# ME433_chip_board.net
KiCad netlist of a schematic drawn in EAGLE
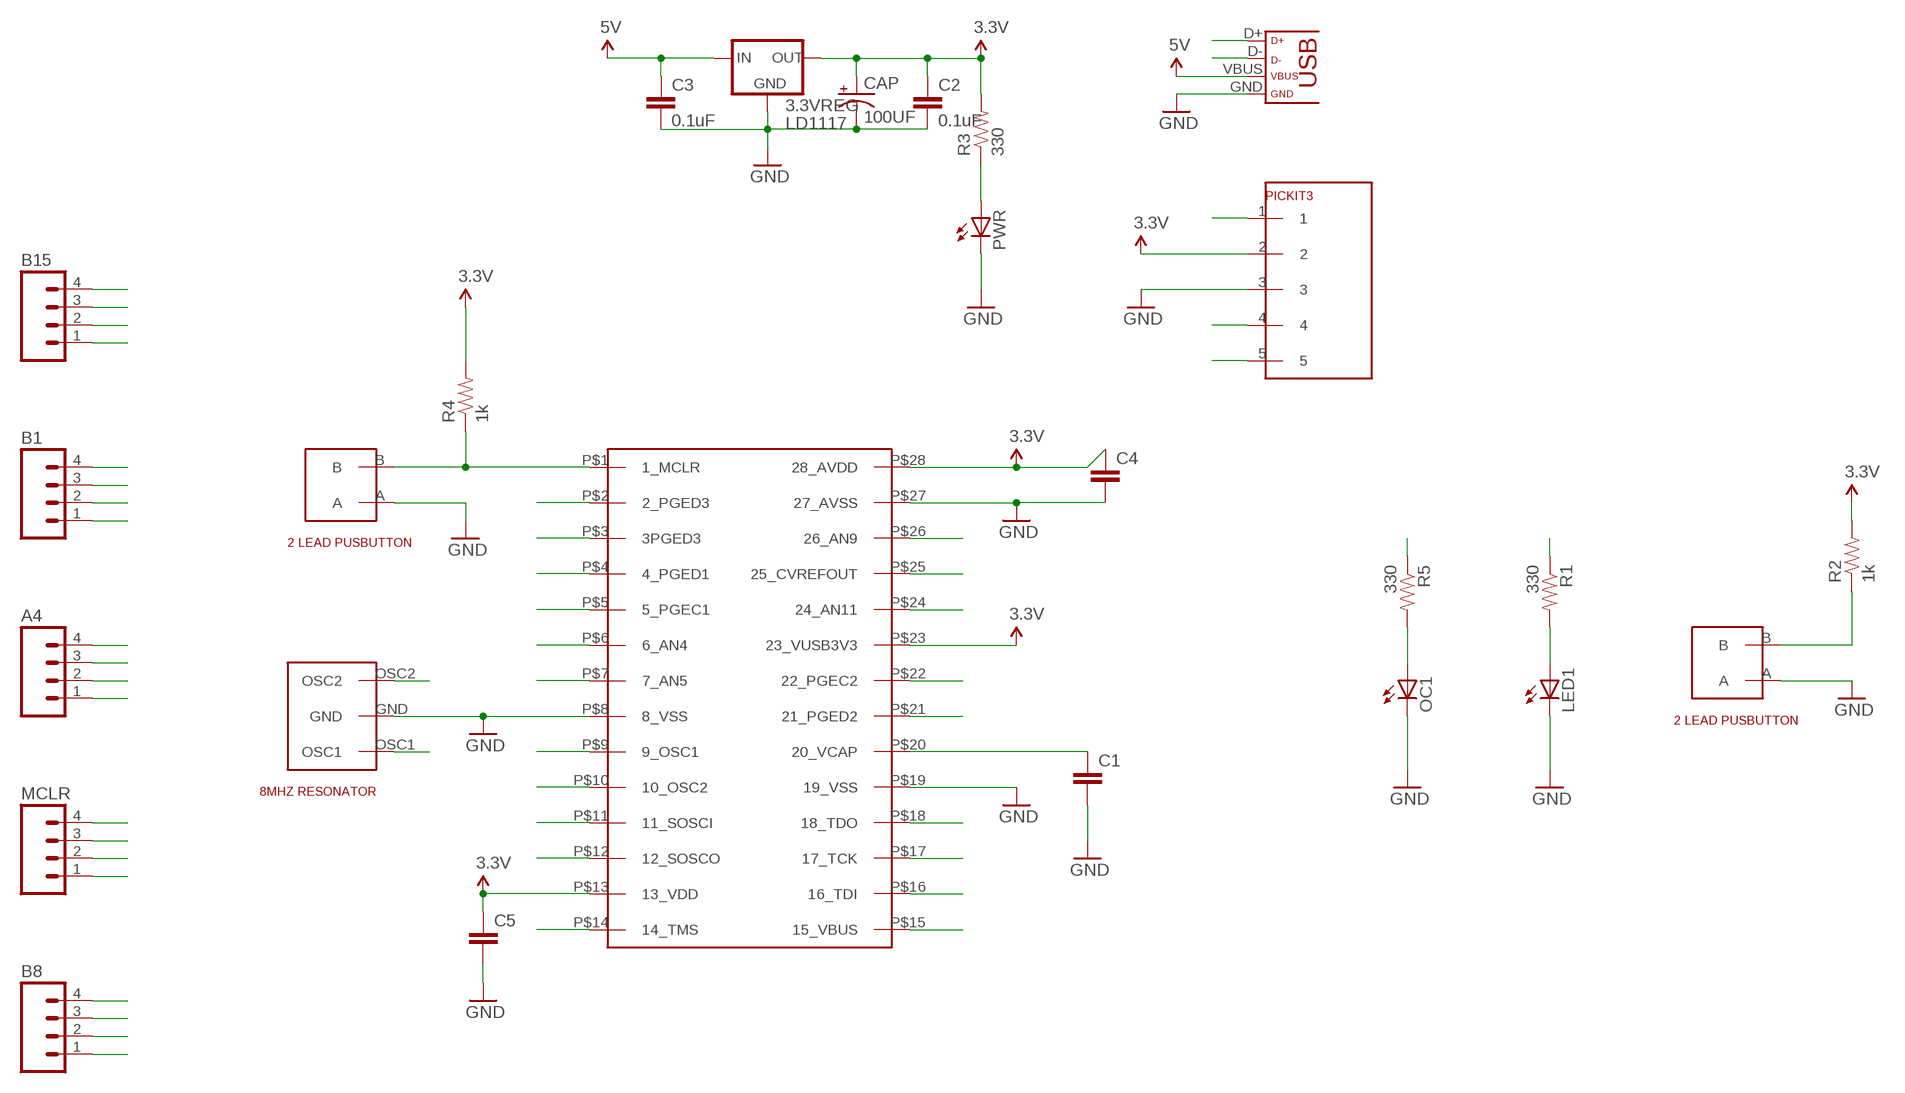
[diagram p0: schematic, sheet 1]

(export (version "E")
  (design (tool "Eeschema 10.0.6"))
  (components
    (comp (ref "3.3VREG")
      (value "LD1117")
      (footprint "eagle-import:TO220")
      (libsource (lib "eagle-import") (part "LD1117"))
    )
    (comp (ref "A4")
      (value "M04PTH")
      (footprint "eagle-import:1X04")
      (libsource (lib "eagle-import") (part "M04PTH"))
    )
    (comp (ref "B1")
      (value "M04PTH")
      (footprint "eagle-import:1X04")
      (libsource (lib "eagle-import") (part "M04PTH"))
    )
    (comp (ref "B8")
      (value "M04PTH")
      (footprint "eagle-import:1X04")
      (libsource (lib "eagle-import") (part "M04PTH"))
    )
    (comp (ref "B15")
      (value "M04PTH")
      (footprint "eagle-import:1X04")
      (libsource (lib "eagle-import") (part "M04PTH"))
    )
    (comp (ref "C1")
      (value "CAP0603-CAP")
      (footprint "eagle-import:0603-CAP")
      (libsource (lib "eagle-import") (part "CAP0603-CAP"))
    )
    (comp (ref "C2")
      (value "0.1uF")
      (footprint "eagle-import:0603-CAP")
      (libsource (lib "eagle-import") (part "CAP0603-CAP"))
    )
    (comp (ref "C3")
      (value "0.1uF")
      (footprint "eagle-import:0603-CAP")
      (libsource (lib "eagle-import") (part "CAP0603-CAP"))
    )
    (comp (ref "C4")
      (value "CAP0603-CAP")
      (footprint "eagle-import:0603-CAP")
      (libsource (lib "eagle-import") (part "CAP0603-CAP"))
    )
    (comp (ref "C5")
      (value "CAP0603-CAP")
      (footprint "eagle-import:0603-CAP")
      (libsource (lib "eagle-import") (part "CAP0603-CAP"))
    )
    (comp (ref "CAP")
      (value "100UF")
      (footprint "eagle-import:CAP_POL_D")
      (libsource (lib "eagle-import") (part "CAP_POL"))
    )
    (comp (ref "LED1")
      (value "TLLR4400")
      (footprint "eagle-import:LED3MM")
      (fields (field (name "MF") "VISHAY SEMICONDUCTOR"))
      (libsource (lib "eagle-import") (part "TLLR4400"))
    )
    (comp (ref "MCLR")
      (value "M04PTH")
      (footprint "eagle-import:1X04")
      (libsource (lib "eagle-import") (part "M04PTH"))
    )
    (comp (ref "OC1")
      (value "TLLR4400")
      (footprint "eagle-import:LED3MM")
      (fields (field (name "MF") "VISHAY SEMICONDUCTOR"))
      (libsource (lib "eagle-import") (part "TLLR4400"))
    )
    (comp (ref "PICKIT3")
      (value "1X05_HEADER")
      (footprint "eagle-import:1X05")
      (libsource (lib "eagle-import") (part "1X05_HEADER"))
    )
    (comp (ref "PWR")
      (value "TLLY4400")
      (footprint "eagle-import:LED3MM")
      (fields (field (name "MF") "VISHAY SEMICONDUCTOR"))
      (libsource (lib "eagle-import") (part "TLLY4400"))
    )
    (comp (ref "R1")
      (value "330")
      (footprint "eagle-import:0603-RES")
      (libsource (lib "eagle-import") (part "RESISTOR0603"))
    )
    (comp (ref "R2")
      (value "1k")
      (footprint "eagle-import:0603-RES")
      (libsource (lib "eagle-import") (part "RESISTOR0603"))
    )
    (comp (ref "R3")
      (value "330")
      (footprint "eagle-import:0603-RES")
      (libsource (lib "eagle-import") (part "RESISTOR0603"))
    )
    (comp (ref "R4")
      (value "1k")
      (footprint "eagle-import:0603-RES")
      (libsource (lib "eagle-import") (part "RESISTOR0603"))
    )
    (comp (ref "R5")
      (value "330")
      (footprint "eagle-import:0603-RES")
      (libsource (lib "eagle-import") (part "RESISTOR0603"))
    )
    (comp (ref "U$1")
      (value "PIC32MX250F128B")
      (footprint "eagle-import:PIC32MX250F128B")
      (libsource (lib "eagle-import") (part "PIC32MX250F128B"))
    )
    (comp (ref "U$3")
      (value "2LEAD_PUSHBUTTON")
      (footprint "eagle-import:2LEAD_PUSHBUTTON")
      (libsource (lib "eagle-import") (part "2LEAD_PUSHBUTTON"))
    )
    (comp (ref "U$6")
      (value "8MHZ_RESONATOR")
      (footprint "eagle-import:8MHZ_RESONATOR")
      (libsource (lib "eagle-import") (part "8MHZ_RESONATOR"))
    )
    (comp (ref "U$7")
      (value "2LEAD_PUSHBUTTON")
      (footprint "eagle-import:2LEAD_PUSHBUTTON")
      (libsource (lib "eagle-import") (part "2LEAD_PUSHBUTTON"))
    )
    (comp (ref "USB")
      (value "USB")
      (footprint "eagle-import:USB-MINIB")
      (libsource (lib "eagle-import") (part "USB"))
    )
  )
  (nets
    (net (code "1") (name "/A0") (class "Default")
      (node (ref "B15") (pin "3") (pinfunction "3_3") (pintype "passive"))
      (node (ref "U$1") (pin "P$2") (pinfunction "2_PGED3_P$2") (pintype "bidirectional"))
    )
    (net (code "2") (name "/A1") (class "Default")
      (node (ref "B15") (pin "2") (pinfunction "2_2") (pintype "passive"))
      (node (ref "U$1") (pin "P$3") (pinfunction "3PGED3_P$3") (pintype "bidirectional"))
    )
    (net (code "3") (name "/A4") (class "Default")
      (node (ref "A4") (pin "4") (pinfunction "4_4") (pintype "passive"))
      (node (ref "U$1") (pin "P$12") (pinfunction "12_SOSCO_P$12") (pintype "bidirectional"))
    )
    (net (code "4") (name "/B0") (class "Default")
      (node (ref "B15") (pin "1") (pinfunction "1_1") (pintype "passive"))
      (node (ref "PICKIT3") (pin "4") (pinfunction "4_4") (pintype "bidirectional"))
      (node (ref "U$1") (pin "P$4") (pinfunction "4_PGED1_P$4") (pintype "bidirectional"))
    )
    (net (code "5") (name "/B1") (class "Default")
      (node (ref "B1") (pin "4") (pinfunction "4_4") (pintype "passive"))
      (node (ref "PICKIT3") (pin "5") (pinfunction "5_5") (pintype "bidirectional"))
      (node (ref "U$1") (pin "P$5") (pinfunction "5_PGEC1_P$5") (pintype "bidirectional"))
    )
    (net (code "6") (name "/B2") (class "Default")
      (node (ref "B1") (pin "3") (pinfunction "3_3") (pintype "passive"))
      (node (ref "U$1") (pin "P$6") (pinfunction "6_AN4_P$6") (pintype "bidirectional"))
    )
    (net (code "7") (name "/B3") (class "Default")
      (node (ref "B1") (pin "2") (pinfunction "2_2") (pintype "passive"))
      (node (ref "U$1") (pin "P$7") (pinfunction "7_AN5_P$7") (pintype "bidirectional"))
    )
    (net (code "8") (name "/B4") (class "Default")
      (node (ref "B1") (pin "1") (pinfunction "1_1") (pintype "passive"))
      (node (ref "U$1") (pin "P$11") (pinfunction "11_SOSCI_P$11") (pintype "bidirectional"))
    )
    (net (code "9") (name "/B5") (class "Default")
      (node (ref "A4") (pin "3") (pinfunction "3_3") (pintype "passive"))
      (node (ref "U$1") (pin "P$14") (pinfunction "14_TMS_P$14") (pintype "bidirectional"))
    )
    (net (code "10") (name "/B7") (class "Default")
      (node (ref "B8") (pin "3") (pinfunction "3_3") (pintype "passive"))
      (node (ref "R1") (pin "1") (pinfunction "1_1") (pintype "passive"))
      (node (ref "U$1") (pin "P$16") (pinfunction "16_TDI_P$16") (pintype "bidirectional"))
    )
    (net (code "11") (name "/B8") (class "Default")
      (node (ref "B8") (pin "4") (pinfunction "4_4") (pintype "passive"))
      (node (ref "U$1") (pin "P$17") (pinfunction "17_TCK_P$17") (pintype "bidirectional"))
    )
    (net (code "12") (name "/B9") (class "Default")
      (node (ref "MCLR") (pin "1") (pinfunction "1_1") (pintype "passive"))
      (node (ref "U$1") (pin "P$18") (pinfunction "18_TDO_P$18") (pintype "bidirectional"))
    )
    (net (code "13") (name "/B13") (class "Default")
      (node (ref "MCLR") (pin "2") (pinfunction "2_2") (pintype "passive"))
      (node (ref "R2") (pin "1") (pinfunction "1_1") (pintype "passive"))
      (node (ref "U$1") (pin "P$24") (pinfunction "24_AN11_P$24") (pintype "bidirectional"))
      (node (ref "U$7") (pin "B") (pinfunction "B_B") (pintype "bidirectional"))
    )
    (net (code "14") (name "/B14") (class "Default")
      (node (ref "MCLR") (pin "3") (pinfunction "3_3") (pintype "passive"))
      (node (ref "U$1") (pin "P$25") (pinfunction "25_CVREFOUT_P$25") (pintype "bidirectional"))
    )
    (net (code "15") (name "/B15") (class "Default")
      (node (ref "MCLR") (pin "4") (pinfunction "4_4") (pintype "passive"))
      (node (ref "R5") (pin "1") (pinfunction "1_1") (pintype "passive"))
      (node (ref "U$1") (pin "P$26") (pinfunction "26_AN9_P$26") (pintype "bidirectional"))
    )
    (net (code "16") (name "/D+") (class "Default")
      (node (ref "U$1") (pin "P$21") (pinfunction "21_PGED2_P$21") (pintype "bidirectional"))
      (node (ref "USB") (pin "D+") (pinfunction "D+_D+") (pintype "bidirectional"))
    )
    (net (code "17") (name "/D-") (class "Default")
      (node (ref "U$1") (pin "P$22") (pinfunction "22_PGEC2_P$22") (pintype "bidirectional"))
      (node (ref "USB") (pin "D-") (pinfunction "D-_D-") (pintype "bidirectional"))
    )
    (net (code "18") (name "/MCLR") (class "Default")
      (node (ref "B15") (pin "4") (pinfunction "4_4") (pintype "passive"))
      (node (ref "PICKIT3") (pin "1") (pinfunction "1_1") (pintype "bidirectional"))
      (node (ref "R4") (pin "1") (pinfunction "1_1") (pintype "passive"))
      (node (ref "U$1") (pin "P$1") (pinfunction "1_MCLR_P$1") (pintype "bidirectional"))
      (node (ref "U$3") (pin "B") (pinfunction "B_B") (pintype "bidirectional"))
    )
    (net (code "19") (name "/OSC1") (class "Default")
      (node (ref "U$1") (pin "P$9") (pinfunction "9_OSC1_P$9") (pintype "bidirectional"))
      (node (ref "U$6") (pin "OSC1") (pinfunction "OSC1_OSC1") (pintype "bidirectional"))
    )
    (net (code "20") (name "/OSC2") (class "Default")
      (node (ref "U$1") (pin "P$10") (pinfunction "10_OSC2_P$10") (pintype "bidirectional"))
      (node (ref "U$6") (pin "OSC2") (pinfunction "OSC2_OSC2") (pintype "bidirectional"))
    )
    (net (code "21") (name "3.3V") (class "Default")
      (node (ref "3.3VREG") (pin "2") (pinfunction "OUT_2") (pintype "output"))
      (node (ref "A4") (pin "1") (pinfunction "1_1") (pintype "passive"))
      (node (ref "C2") (pin "1") (pinfunction "1_1") (pintype "passive"))
      (node (ref "C4") (pin "1") (pinfunction "1_1") (pintype "passive"))
      (node (ref "C5") (pin "1") (pinfunction "1_1") (pintype "passive"))
      (node (ref "CAP") (pin "1") (pinfunction "+_1") (pintype "passive"))
      (node (ref "PICKIT3") (pin "2") (pinfunction "2_2") (pintype "bidirectional"))
      (node (ref "R2") (pin "2") (pinfunction "2_2") (pintype "passive"))
      (node (ref "R3") (pin "2") (pinfunction "2_2") (pintype "passive"))
      (node (ref "R4") (pin "2") (pinfunction "2_2") (pintype "passive"))
      (node (ref "U$1") (pin "P$13") (pinfunction "13_VDD_P$13") (pintype "bidirectional"))
      (node (ref "U$1") (pin "P$23") (pinfunction "23_VUSB3V3_P$23") (pintype "bidirectional"))
      (node (ref "U$1") (pin "P$28") (pinfunction "28_AVDD_P$28") (pintype "bidirectional"))
    )
    (net (code "22") (name "5V") (class "Default")
      (node (ref "3.3VREG") (pin "3") (pinfunction "IN_3") (pintype "input"))
      (node (ref "B8") (pin "1") (pinfunction "1_1") (pintype "passive"))
      (node (ref "C3") (pin "1") (pinfunction "1_1") (pintype "passive"))
      (node (ref "U$1") (pin "P$15") (pinfunction "15_VBUS_P$15") (pintype "bidirectional"))
      (node (ref "USB") (pin "VBUS") (pinfunction "VBUS_VBUS") (pintype "bidirectional"))
    )
    (net (code "23") (name "GND") (class "Default")
      (node (ref "3.3VREG") (pin "1") (pinfunction "GND_1") (pintype "input"))
      (node (ref "A4") (pin "2") (pinfunction "2_2") (pintype "passive"))
      (node (ref "B8") (pin "2") (pinfunction "2_2") (pintype "passive"))
      (node (ref "C1") (pin "2") (pinfunction "2_2") (pintype "passive"))
      (node (ref "C2") (pin "2") (pinfunction "2_2") (pintype "passive"))
      (node (ref "C3") (pin "2") (pinfunction "2_2") (pintype "passive"))
      (node (ref "C4") (pin "2") (pinfunction "2_2") (pintype "passive"))
      (node (ref "C5") (pin "2") (pinfunction "2_2") (pintype "passive"))
      (node (ref "CAP") (pin "2") (pinfunction "-_2") (pintype "passive"))
      (node (ref "LED1") (pin "K") (pinfunction "C_K") (pintype "passive"))
      (node (ref "OC1") (pin "K") (pinfunction "C_K") (pintype "passive"))
      (node (ref "PICKIT3") (pin "3") (pinfunction "3_3") (pintype "bidirectional"))
      (node (ref "PWR") (pin "K") (pinfunction "C_K") (pintype "passive"))
      (node (ref "U$1") (pin "P$19") (pinfunction "19_VSS_P$19") (pintype "bidirectional"))
      (node (ref "U$1") (pin "P$27") (pinfunction "27_AVSS_P$27") (pintype "bidirectional"))
      (node (ref "U$1") (pin "P$8") (pinfunction "8_VSS_P$8") (pintype "bidirectional"))
      (node (ref "U$3") (pin "A") (pinfunction "A_A") (pintype "bidirectional"))
      (node (ref "U$6") (pin "GND") (pinfunction "GND_GND") (pintype "bidirectional"))
      (node (ref "U$7") (pin "A") (pinfunction "A_A") (pintype "bidirectional"))
      (node (ref "USB") (pin "GND") (pinfunction "GND_GND") (pintype "bidirectional"))
    )
    (net (code "24") (name "Net-(LED1-PadA)") (class "Default")
      (node (ref "LED1") (pin "A") (pinfunction "A_A") (pintype "passive"))
      (node (ref "R1") (pin "2") (pinfunction "2_2") (pintype "passive"))
    )
    (net (code "25") (name "Net-(OC1-PadA)") (class "Default")
      (node (ref "OC1") (pin "A") (pinfunction "A_A") (pintype "passive"))
      (node (ref "R5") (pin "2") (pinfunction "2_2") (pintype "passive"))
    )
    (net (code "26") (name "Net-(PWR-PadA)") (class "Default")
      (node (ref "PWR") (pin "A") (pinfunction "A_A") (pintype "passive"))
      (node (ref "R3") (pin "1") (pinfunction "1_1") (pintype "passive"))
    )
    (net (code "27") (name "Net-(U$1-20_VCAP)") (class "Default")
      (node (ref "C1") (pin "1") (pinfunction "1_1") (pintype "passive"))
      (node (ref "U$1") (pin "P$20") (pinfunction "20_VCAP_P$20") (pintype "bidirectional"))
    )
  )
)
